# CV2018-DIFF.net
KiCad netlist of a schematic drawn in Altium Designer
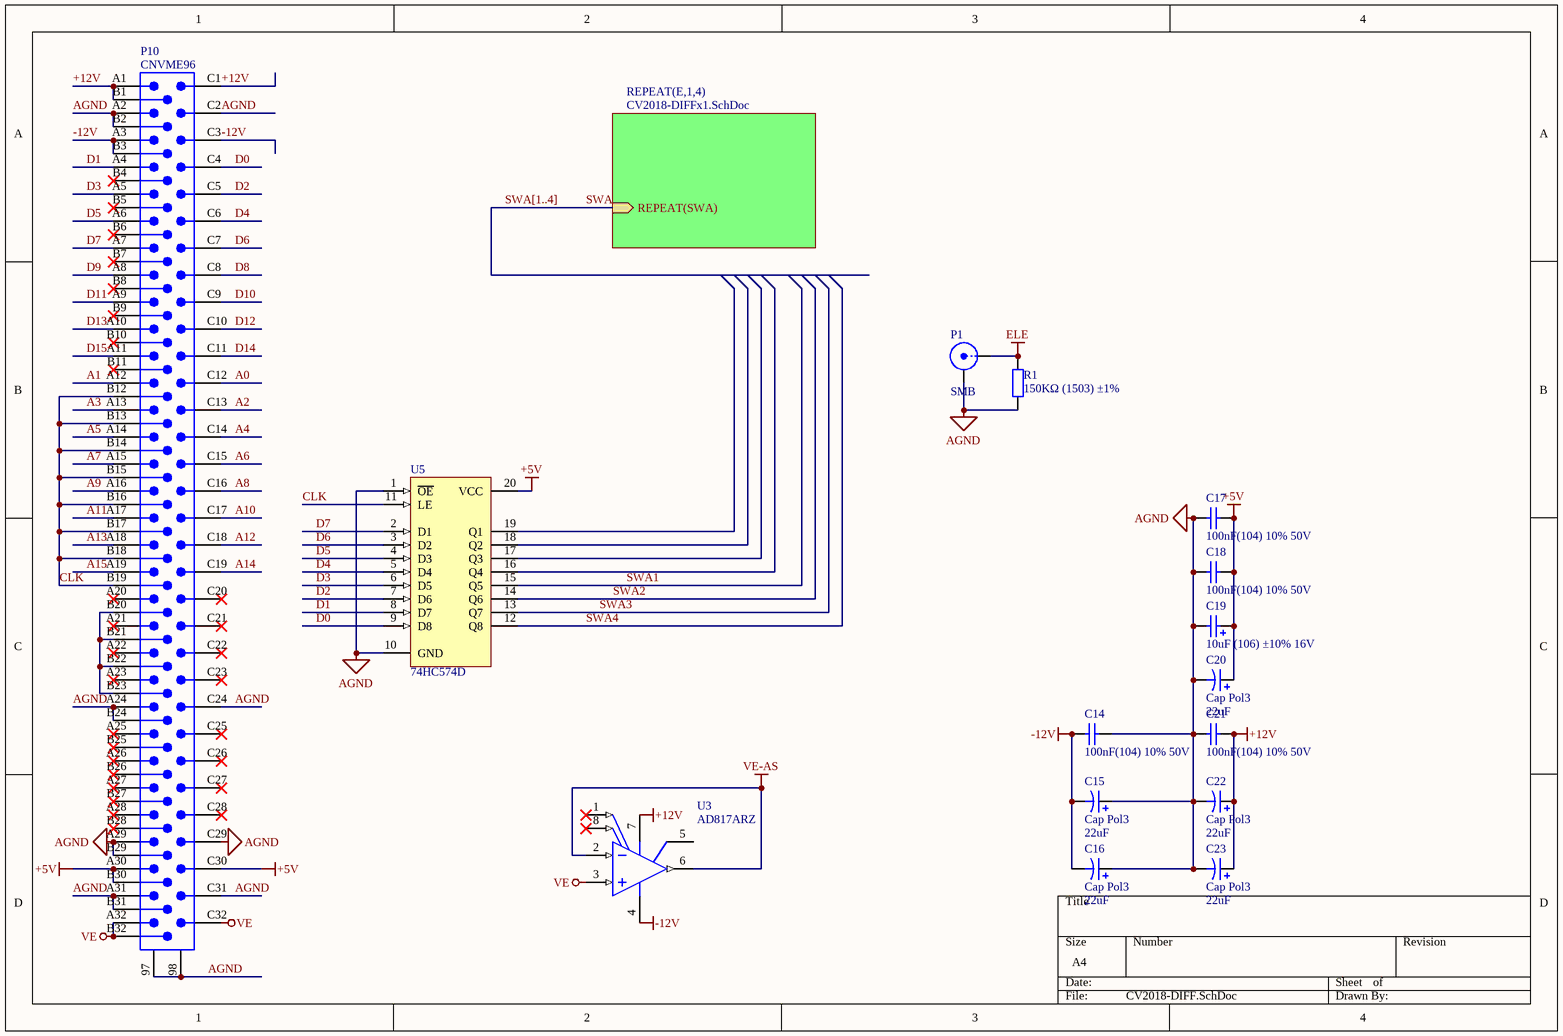
[diagram p0: CV2018-DIFF.SchDoc]

(export (version "E")
  (design (tool "Eeschema 10.0.6"))
  (components
    (comp (ref "C14")
      (value "100nF(104) 10% 50V")
      (footprint "LC-0805_C")
      (description "贴片电容")
      (libsource (lib "Miscellaneous Devices LC") (part "0805 100nF(104) 10% 50V"))
    )
    (comp (ref "C15")
      (value "Cap Pol3")
      (footprint "C2225")
      (description "Polarized Capacitor (Surface Mount)")
      (fields (field (name "ALTIUM_VALUE") "22uF") (field (name "PUBLISHER") "Altium Limited"))
      (libsource (lib "Miscellaneous Devices") (part "Cap Pol3"))
    )
    (comp (ref "C16")
      (value "Cap Pol3")
      (footprint "C2225")
      (description "Polarized Capacitor (Surface Mount)")
      (fields (field (name "ALTIUM_VALUE") "22uF") (field (name "PUBLISHER") "Altium Limited"))
      (libsource (lib "Miscellaneous Devices") (part "Cap Pol3"))
    )
    (comp (ref "C17")
      (value "100nF(104) 10% 50V")
      (footprint "LC-0805_C")
      (description "贴片电容")
      (libsource (lib "Miscellaneous Devices LC") (part "0805 100nF(104) 10% 50V"))
    )
    (comp (ref "C18")
      (value "100nF(104) 10% 50V")
      (footprint "LC-0805_C")
      (description "贴片电容")
      (libsource (lib "Miscellaneous Devices LC") (part "0805 100nF(104) 10% 50V"))
    )
    (comp (ref "C19")
      (value "10uF (106) ±10% 16V")
      (footprint "LC-CASE-A_3216")
      (description "钽电容")
      (libsource (lib "Miscellaneous Devices LC") (part "3216 10uF (106) 10% 16V"))
    )
    (comp (ref "C20")
      (value "Cap Pol3")
      (footprint "C2225")
      (description "Polarized Capacitor (Surface Mount)")
      (fields (field (name "ALTIUM_VALUE") "22uF") (field (name "PUBLISHER") "Altium Limited"))
      (libsource (lib "Miscellaneous Devices") (part "Cap Pol3"))
    )
    (comp (ref "C21")
      (value "100nF(104) 10% 50V")
      (footprint "LC-0805_C")
      (description "贴片电容")
      (libsource (lib "Miscellaneous Devices LC") (part "0805 100nF(104) 10% 50V"))
    )
    (comp (ref "C22")
      (value "Cap Pol3")
      (footprint "C2225")
      (description "Polarized Capacitor (Surface Mount)")
      (fields (field (name "ALTIUM_VALUE") "22uF") (field (name "PUBLISHER") "Altium Limited"))
      (libsource (lib "Miscellaneous Devices") (part "Cap Pol3"))
    )
    (comp (ref "C23")
      (value "Cap Pol3")
      (footprint "C2225")
      (description "Polarized Capacitor (Surface Mount)")
      (fields (field (name "ALTIUM_VALUE") "22uF") (field (name "PUBLISHER") "Altium Limited"))
      (libsource (lib "Miscellaneous Devices") (part "Cap Pol3"))
    )
    (comp (ref "P1")
      (value "SMB")
      (footprint "SMB_V-RJ45")
      (description "SMB Straight Connector")
      (fields (field (name "PUBLISHER") "Altium Limited"))
      (libsource (lib "Miscellaneous Connectors") (part "SMB"))
    )
    (comp (ref "P10")
      (value "CNVME96")
      (footprint "CNVME96")
      (description "96-Pin Connector (3x32 2.54mm grid)")
      (libsource (lib "*") (part "CNVME96"))
    )
    (comp (ref "R1")
      (value "150KΩ (1503) ±1%")
      (footprint "LC-0805_R")
      (description "贴片电阻")
      (libsource (lib "Miscellaneous Devices LC") (part "0805 150KΩ (1503) 1%"))
    )
    (comp (ref "U3")
      (value "AD817ARZ")
      (footprint "ADI-R-8_N")
      (fields (field (name "GENERIC PART NUMBER") "AD817") (field (name "MANUFACTURER") "Analog Devices"))
      (libsource (lib "Analog Devices Operational Amplifiers") (part "AD817ARZ"))
    )
    (comp (ref "U5")
      (value "74HC574D")
      (footprint "LC-SOIC-20_300mil")
      (description "74系列逻辑芯片")
      (libsource (lib "Miscellaneous Devices LC") (part "74HC573D"))
    )
  )
  (nets
    (net (code "1") (name "+5V") (class "Default")
      (node (ref "C17") (pin "2") (pinfunction "2_2") (pintype "passive"))
      (node (ref "C18") (pin "2") (pinfunction "2_2") (pintype "passive"))
      (node (ref "C19") (pin "1") (pinfunction "1_1") (pintype "passive"))
      (node (ref "C20") (pin "1") (pinfunction "1_1") (pintype "passive"))
      (node (ref "P10") (pin "A30") (pinfunction "A30_A30") (pintype "passive"))
      (node (ref "P10") (pin "B30") (pinfunction "B30_B30") (pintype "passive"))
      (node (ref "P10") (pin "C30") (pinfunction "C30_C30") (pintype "passive"))
      (node (ref "U5") (pin "20") (pinfunction "VCC_20") (pintype "power_in"))
    )
    (net (code "2") (name "+12V") (class "Default")
      (node (ref "C21") (pin "2") (pinfunction "2_2") (pintype "passive"))
      (node (ref "C22") (pin "1") (pinfunction "1_1") (pintype "passive"))
      (node (ref "C23") (pin "1") (pinfunction "1_1") (pintype "passive"))
      (node (ref "P10") (pin "A1") (pinfunction "A1_A1") (pintype "passive"))
      (node (ref "P10") (pin "B1") (pinfunction "B1_B1") (pintype "passive"))
      (node (ref "P10") (pin "C1") (pinfunction "C1_C1") (pintype "passive"))
      (node (ref "U3") (pin "7") (pinfunction "+VS_7") (pintype "power_in"))
    )
    (net (code "3") (name "-12V") (class "Default")
      (node (ref "C14") (pin "1") (pinfunction "1_1") (pintype "passive"))
      (node (ref "C15") (pin "2") (pinfunction "2_2") (pintype "passive"))
      (node (ref "C16") (pin "2") (pinfunction "2_2") (pintype "passive"))
      (node (ref "P10") (pin "A3") (pinfunction "A3_A3") (pintype "passive"))
      (node (ref "P10") (pin "B3") (pinfunction "B3_B3") (pintype "passive"))
      (node (ref "P10") (pin "C3") (pinfunction "C3_C3") (pintype "passive"))
      (node (ref "U3") (pin "4") (pinfunction "-VS_4") (pintype "power_in"))
    )
    (net (code "4") (name "/A0") (class "Default")
      (node (ref "P10") (pin "C12") (pinfunction "C12_C12") (pintype "passive"))
    )
    (net (code "5") (name "/A1") (class "Default")
      (node (ref "P10") (pin "A12") (pinfunction "A12_A12") (pintype "passive"))
    )
    (net (code "6") (name "/A2") (class "Default")
      (node (ref "P10") (pin "C13") (pinfunction "C13_C13") (pintype "passive"))
    )
    (net (code "7") (name "/A3") (class "Default")
      (node (ref "P10") (pin "A13") (pinfunction "A13_A13") (pintype "passive"))
    )
    (net (code "8") (name "/A4") (class "Default")
      (node (ref "P10") (pin "C14") (pinfunction "C14_C14") (pintype "passive"))
    )
    (net (code "9") (name "/A5") (class "Default")
      (node (ref "P10") (pin "A14") (pinfunction "A14_A14") (pintype "passive"))
    )
    (net (code "10") (name "/A6") (class "Default")
      (node (ref "P10") (pin "C15") (pinfunction "C15_C15") (pintype "passive"))
    )
    (net (code "11") (name "/A7") (class "Default")
      (node (ref "P10") (pin "A15") (pinfunction "A15_A15") (pintype "passive"))
    )
    (net (code "12") (name "/A8") (class "Default")
      (node (ref "P10") (pin "C16") (pinfunction "C16_C16") (pintype "passive"))
    )
    (net (code "13") (name "/A9") (class "Default")
      (node (ref "P10") (pin "A16") (pinfunction "A16_A16") (pintype "passive"))
    )
    (net (code "14") (name "/A10") (class "Default")
      (node (ref "P10") (pin "C17") (pinfunction "C17_C17") (pintype "passive"))
    )
    (net (code "15") (name "/A11") (class "Default")
      (node (ref "P10") (pin "A17") (pinfunction "A17_A17") (pintype "passive"))
    )
    (net (code "16") (name "/A12") (class "Default")
      (node (ref "P10") (pin "C18") (pinfunction "C18_C18") (pintype "passive"))
    )
    (net (code "17") (name "/A13") (class "Default")
      (node (ref "P10") (pin "A18") (pinfunction "A18_A18") (pintype "passive"))
    )
    (net (code "18") (name "/A14") (class "Default")
      (node (ref "P10") (pin "C19") (pinfunction "C19_C19") (pintype "passive"))
    )
    (net (code "19") (name "/A15") (class "Default")
      (node (ref "P10") (pin "A19") (pinfunction "A19_A19") (pintype "passive"))
    )
    (net (code "20") (name "/CLK") (class "Default")
      (node (ref "P10") (pin "B12") (pinfunction "B12_B12") (pintype "passive"))
      (node (ref "P10") (pin "B13") (pinfunction "B13_B13") (pintype "passive"))
      (node (ref "P10") (pin "B14") (pinfunction "B14_B14") (pintype "passive"))
      (node (ref "P10") (pin "B15") (pinfunction "B15_B15") (pintype "passive"))
      (node (ref "P10") (pin "B16") (pinfunction "B16_B16") (pintype "passive"))
      (node (ref "P10") (pin "B17") (pinfunction "B17_B17") (pintype "passive"))
      (node (ref "P10") (pin "B18") (pinfunction "B18_B18") (pintype "passive"))
      (node (ref "P10") (pin "B19") (pinfunction "B19_B19") (pintype "passive"))
      (node (ref "U5") (pin "11") (pinfunction "LE_11") (pintype "input"))
    )
    (net (code "21") (name "/D0") (class "Default")
      (node (ref "P10") (pin "C4") (pinfunction "C4_C4") (pintype "passive"))
      (node (ref "U5") (pin "9") (pinfunction "D8_9") (pintype "input"))
    )
    (net (code "22") (name "/D1") (class "Default")
      (node (ref "P10") (pin "A4") (pinfunction "A4_A4") (pintype "passive"))
      (node (ref "U5") (pin "8") (pinfunction "D7_8") (pintype "input"))
    )
    (net (code "23") (name "/D2") (class "Default")
      (node (ref "P10") (pin "C5") (pinfunction "C5_C5") (pintype "passive"))
      (node (ref "U5") (pin "7") (pinfunction "D6_7") (pintype "input"))
    )
    (net (code "24") (name "/D3") (class "Default")
      (node (ref "P10") (pin "A5") (pinfunction "A5_A5") (pintype "passive"))
      (node (ref "U5") (pin "6") (pinfunction "D5_6") (pintype "input"))
    )
    (net (code "25") (name "/D4") (class "Default")
      (node (ref "P10") (pin "C6") (pinfunction "C6_C6") (pintype "passive"))
      (node (ref "U5") (pin "5") (pinfunction "D4_5") (pintype "input"))
    )
    (net (code "26") (name "/D5") (class "Default")
      (node (ref "P10") (pin "A6") (pinfunction "A6_A6") (pintype "passive"))
      (node (ref "U5") (pin "4") (pinfunction "D3_4") (pintype "input"))
    )
    (net (code "27") (name "/D6") (class "Default")
      (node (ref "P10") (pin "C7") (pinfunction "C7_C7") (pintype "passive"))
      (node (ref "U5") (pin "3") (pinfunction "D2_3") (pintype "input"))
    )
    (net (code "28") (name "/D7") (class "Default")
      (node (ref "P10") (pin "A7") (pinfunction "A7_A7") (pintype "passive"))
      (node (ref "U5") (pin "2") (pinfunction "D1_2") (pintype "input"))
    )
    (net (code "29") (name "/D8") (class "Default")
      (node (ref "P10") (pin "C8") (pinfunction "C8_C8") (pintype "passive"))
    )
    (net (code "30") (name "/D9") (class "Default")
      (node (ref "P10") (pin "A8") (pinfunction "A8_A8") (pintype "passive"))
    )
    (net (code "31") (name "/D10") (class "Default")
      (node (ref "P10") (pin "C9") (pinfunction "C9_C9") (pintype "passive"))
    )
    (net (code "32") (name "/D11") (class "Default")
      (node (ref "P10") (pin "A9") (pinfunction "A9_A9") (pintype "passive"))
    )
    (net (code "33") (name "/D12") (class "Default")
      (node (ref "P10") (pin "C10") (pinfunction "C10_C10") (pintype "passive"))
    )
    (net (code "34") (name "/D13") (class "Default")
      (node (ref "P10") (pin "A10") (pinfunction "A10_A10") (pintype "passive"))
    )
    (net (code "35") (name "/D14") (class "Default")
      (node (ref "P10") (pin "C11") (pinfunction "C11_C11") (pintype "passive"))
    )
    (net (code "36") (name "/D15") (class "Default")
      (node (ref "P10") (pin "A11") (pinfunction "A11_A11") (pintype "passive"))
    )
    (net (code "38") (name "/SWA1") (class "Default")
      (node (ref "U5") (pin "15") (pinfunction "Q5_15") (pintype "tri_state"))
    )
    (net (code "39") (name "/SWA2") (class "Default")
      (node (ref "U5") (pin "14") (pinfunction "Q6_14") (pintype "tri_state"))
    )
    (net (code "40") (name "/SWA3") (class "Default")
      (node (ref "U5") (pin "13") (pinfunction "Q7_13") (pintype "tri_state"))
    )
    (net (code "41") (name "/SWA4") (class "Default")
      (node (ref "U5") (pin "12") (pinfunction "Q8_12") (pintype "tri_state"))
    )
    (net (code "43") (name "AGND") (class "Default")
      (node (ref "C14") (pin "2") (pinfunction "2_2") (pintype "passive"))
      (node (ref "C15") (pin "1") (pinfunction "1_1") (pintype "passive"))
      (node (ref "C16") (pin "1") (pinfunction "1_1") (pintype "passive"))
      (node (ref "C17") (pin "1") (pinfunction "1_1") (pintype "passive"))
      (node (ref "C18") (pin "1") (pinfunction "1_1") (pintype "passive"))
      (node (ref "C19") (pin "2") (pinfunction "2_2") (pintype "passive"))
      (node (ref "C20") (pin "2") (pinfunction "2_2") (pintype "passive"))
      (node (ref "C21") (pin "1") (pinfunction "1_1") (pintype "passive"))
      (node (ref "C22") (pin "2") (pinfunction "2_2") (pintype "passive"))
      (node (ref "C23") (pin "2") (pinfunction "2_2") (pintype "passive"))
      (node (ref "P1") (pin "2") (pinfunction "Y_2") (pintype "passive"))
      (node (ref "P10") (pin "97") (pinfunction "97_97") (pintype "passive"))
      (node (ref "P10") (pin "98") (pinfunction "98_98") (pintype "passive"))
      (node (ref "P10") (pin "A2") (pinfunction "A2_A2") (pintype "passive"))
      (node (ref "P10") (pin "A24") (pinfunction "A24_A24") (pintype "passive"))
      (node (ref "P10") (pin "A29") (pinfunction "A29_A29") (pintype "passive"))
      (node (ref "P10") (pin "A31") (pinfunction "A31_A31") (pintype "passive"))
      (node (ref "P10") (pin "B2") (pinfunction "B2_B2") (pintype "passive"))
      (node (ref "P10") (pin "B24") (pinfunction "B24_B24") (pintype "passive"))
      (node (ref "P10") (pin "B29") (pinfunction "B29_B29") (pintype "passive"))
      (node (ref "P10") (pin "B31") (pinfunction "B31_B31") (pintype "passive"))
      (node (ref "P10") (pin "C2") (pinfunction "C2_C2") (pintype "passive"))
      (node (ref "P10") (pin "C24") (pinfunction "C24_C24") (pintype "passive"))
      (node (ref "P10") (pin "C29") (pinfunction "C29_C29") (pintype "passive"))
      (node (ref "P10") (pin "C31") (pinfunction "C31_C31") (pintype "passive"))
      (node (ref "R1") (pin "2") (pinfunction "2_2") (pintype "passive"))
      (node (ref "U5") (pin "1") (pinfunction "~{OE}_1") (pintype "input"))
      (node (ref "U5") (pin "10") (pinfunction "GND_10") (pintype "power_in"))
    )
    (net (code "44") (name "ELE") (class "Default")
      (node (ref "P1") (pin "1") (pinfunction "X_1") (pintype "passive"))
      (node (ref "R1") (pin "1") (pinfunction "1_1") (pintype "passive"))
    )
    (net (code "45") (name "Net-(P10-PadB20)") (class "Default")
      (node (ref "P10") (pin "B20") (pinfunction "B20_B20") (pintype "passive"))
      (node (ref "P10") (pin "B21") (pinfunction "B21_B21") (pintype "passive"))
      (node (ref "P10") (pin "B22") (pinfunction "B22_B22") (pintype "passive"))
      (node (ref "P10") (pin "B23") (pinfunction "B23_B23") (pintype "passive"))
    )
    (net (code "46") (name "VE") (class "Default")
      (node (ref "P10") (pin "A32") (pinfunction "A32_A32") (pintype "passive"))
      (node (ref "P10") (pin "B32") (pinfunction "B32_B32") (pintype "passive"))
      (node (ref "P10") (pin "C32") (pinfunction "C32_C32") (pintype "passive"))
      (node (ref "U3") (pin "3") (pinfunction "+IN_3") (pintype "input"))
    )
    (net (code "47") (name "VE-AS") (class "Default")
      (node (ref "U3") (pin "2") (pinfunction "-IN_2") (pintype "input"))
      (node (ref "U3") (pin "6") (pinfunction "OUT_6") (pintype "output"))
    )
    (net (code "48") (name "unconnected-(P10-PadA20)") (class "Default")
      (node (ref "P10") (pin "A20") (pinfunction "A20_A20") (pintype "passive+no_connect"))
    )
    (net (code "49") (name "unconnected-(P10-PadA21)") (class "Default")
      (node (ref "P10") (pin "A21") (pinfunction "A21_A21") (pintype "passive+no_connect"))
    )
    (net (code "50") (name "unconnected-(P10-PadA22)") (class "Default")
      (node (ref "P10") (pin "A22") (pinfunction "A22_A22") (pintype "passive+no_connect"))
    )
    (net (code "51") (name "unconnected-(P10-PadA23)") (class "Default")
      (node (ref "P10") (pin "A23") (pinfunction "A23_A23") (pintype "passive+no_connect"))
    )
    (net (code "52") (name "unconnected-(P10-PadA25)") (class "Default")
      (node (ref "P10") (pin "A25") (pinfunction "A25_A25") (pintype "passive+no_connect"))
    )
    (net (code "53") (name "unconnected-(P10-PadA26)") (class "Default")
      (node (ref "P10") (pin "A26") (pinfunction "A26_A26") (pintype "passive+no_connect"))
    )
    (net (code "54") (name "unconnected-(P10-PadA27)") (class "Default")
      (node (ref "P10") (pin "A27") (pinfunction "A27_A27") (pintype "passive+no_connect"))
    )
    (net (code "55") (name "unconnected-(P10-PadA28)") (class "Default")
      (node (ref "P10") (pin "A28") (pinfunction "A28_A28") (pintype "passive+no_connect"))
    )
    (net (code "56") (name "unconnected-(P10-PadB4)") (class "Default")
      (node (ref "P10") (pin "B4") (pinfunction "B4_B4") (pintype "passive+no_connect"))
    )
    (net (code "57") (name "unconnected-(P10-PadB5)") (class "Default")
      (node (ref "P10") (pin "B5") (pinfunction "B5_B5") (pintype "passive+no_connect"))
    )
    (net (code "58") (name "unconnected-(P10-PadB6)") (class "Default")
      (node (ref "P10") (pin "B6") (pinfunction "B6_B6") (pintype "passive+no_connect"))
    )
    (net (code "59") (name "unconnected-(P10-PadB7)") (class "Default")
      (node (ref "P10") (pin "B7") (pinfunction "B7_B7") (pintype "passive+no_connect"))
    )
    (net (code "60") (name "unconnected-(P10-PadB8)") (class "Default")
      (node (ref "P10") (pin "B8") (pinfunction "B8_B8") (pintype "passive+no_connect"))
    )
    (net (code "61") (name "unconnected-(P10-PadB9)") (class "Default")
      (node (ref "P10") (pin "B9") (pinfunction "B9_B9") (pintype "passive+no_connect"))
    )
    (net (code "62") (name "unconnected-(P10-PadB10)") (class "Default")
      (node (ref "P10") (pin "B10") (pinfunction "B10_B10") (pintype "passive+no_connect"))
    )
    (net (code "63") (name "unconnected-(P10-PadB11)") (class "Default")
      (node (ref "P10") (pin "B11") (pinfunction "B11_B11") (pintype "passive+no_connect"))
    )
    (net (code "64") (name "unconnected-(P10-PadB25)") (class "Default")
      (node (ref "P10") (pin "B25") (pinfunction "B25_B25") (pintype "passive+no_connect"))
    )
    (net (code "65") (name "unconnected-(P10-PadB26)") (class "Default")
      (node (ref "P10") (pin "B26") (pinfunction "B26_B26") (pintype "passive+no_connect"))
    )
    (net (code "66") (name "unconnected-(P10-PadB27)") (class "Default")
      (node (ref "P10") (pin "B27") (pinfunction "B27_B27") (pintype "passive+no_connect"))
    )
    (net (code "67") (name "unconnected-(P10-PadB28)") (class "Default")
      (node (ref "P10") (pin "B28") (pinfunction "B28_B28") (pintype "passive+no_connect"))
    )
    (net (code "68") (name "unconnected-(P10-PadC20)") (class "Default")
      (node (ref "P10") (pin "C20") (pinfunction "C20_C20") (pintype "passive+no_connect"))
    )
    (net (code "69") (name "unconnected-(P10-PadC21)") (class "Default")
      (node (ref "P10") (pin "C21") (pinfunction "C21_C21") (pintype "passive+no_connect"))
    )
    (net (code "70") (name "unconnected-(P10-PadC22)") (class "Default")
      (node (ref "P10") (pin "C22") (pinfunction "C22_C22") (pintype "passive+no_connect"))
    )
    (net (code "71") (name "unconnected-(P10-PadC23)") (class "Default")
      (node (ref "P10") (pin "C23") (pinfunction "C23_C23") (pintype "passive+no_connect"))
    )
    (net (code "72") (name "unconnected-(P10-PadC25)") (class "Default")
      (node (ref "P10") (pin "C25") (pinfunction "C25_C25") (pintype "passive+no_connect"))
    )
    (net (code "73") (name "unconnected-(P10-PadC26)") (class "Default")
      (node (ref "P10") (pin "C26") (pinfunction "C26_C26") (pintype "passive+no_connect"))
    )
    (net (code "74") (name "unconnected-(P10-PadC27)") (class "Default")
      (node (ref "P10") (pin "C27") (pinfunction "C27_C27") (pintype "passive+no_connect"))
    )
    (net (code "75") (name "unconnected-(P10-PadC28)") (class "Default")
      (node (ref "P10") (pin "C28") (pinfunction "C28_C28") (pintype "passive+no_connect"))
    )
    (net (code "76") (name "unconnected-(U3-NC-Pad5)") (class "Default")
      (node (ref "U3") (pin "5") (pinfunction "NC_5") (pintype "passive"))
    )
    (net (code "77") (name "unconnected-(U3-NULL-Pad1)") (class "Default")
      (node (ref "U3") (pin "1") (pinfunction "NULL_1") (pintype "input+no_connect"))
    )
    (net (code "78") (name "unconnected-(U3-NULL-Pad8)") (class "Default")
      (node (ref "U3") (pin "8") (pinfunction "NULL_8") (pintype "input+no_connect"))
    )
    (net (code "79") (name "unconnected-(U5-Q1-Pad19)") (class "Default")
      (node (ref "U5") (pin "19") (pinfunction "Q1_19") (pintype "tri_state"))
    )
    (net (code "80") (name "unconnected-(U5-Q2-Pad18)") (class "Default")
      (node (ref "U5") (pin "18") (pinfunction "Q2_18") (pintype "tri_state"))
    )
    (net (code "81") (name "unconnected-(U5-Q3-Pad17)") (class "Default")
      (node (ref "U5") (pin "17") (pinfunction "Q3_17") (pintype "tri_state"))
    )
    (net (code "82") (name "unconnected-(U5-Q4-Pad16)") (class "Default")
      (node (ref "U5") (pin "16") (pinfunction "Q4_16") (pintype "tri_state"))
    )
  )
)
